# WFT0420CZ15_eval.net
KiCad netlist of a schematic drawn in EAGLE
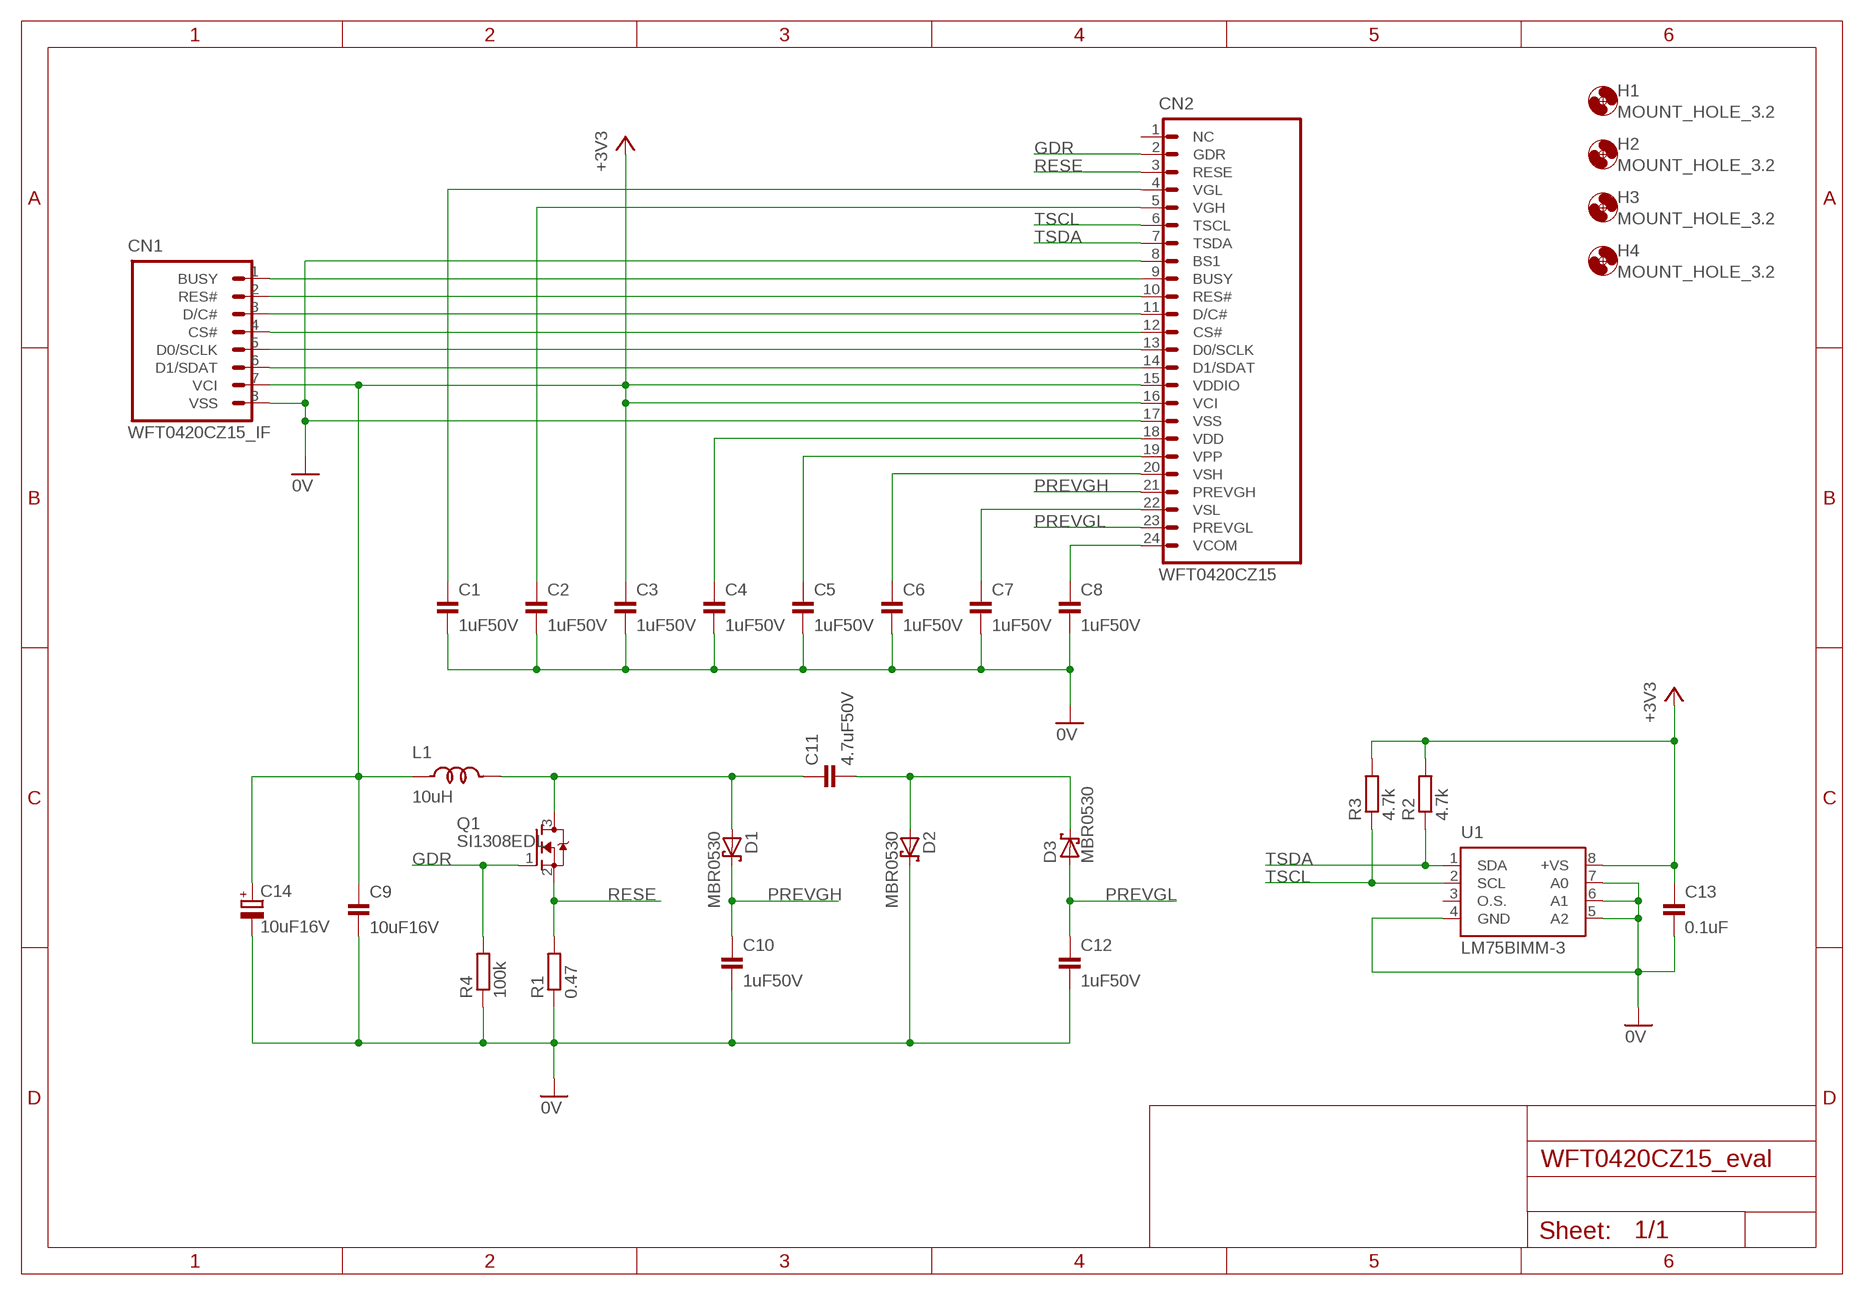
[diagram p0: schematic, sheet 1]

(export (version "E")
  (design (tool "Eeschema 10.0.6"))
  (components
    (comp (ref "C1")
      (value "1uF50V")
      (footprint "eagle-import:SMD_2012")
      (libsource (lib "eagle-import") (part "CAP_0805"))
    )
    (comp (ref "C2")
      (value "1uF50V")
      (footprint "eagle-import:SMD_2012")
      (libsource (lib "eagle-import") (part "CAP_0805"))
    )
    (comp (ref "C3")
      (value "1uF50V")
      (footprint "eagle-import:SMD_2012")
      (libsource (lib "eagle-import") (part "CAP_0805"))
    )
    (comp (ref "C4")
      (value "1uF50V")
      (footprint "eagle-import:SMD_2012")
      (libsource (lib "eagle-import") (part "CAP_0805"))
    )
    (comp (ref "C5")
      (value "1uF50V")
      (footprint "eagle-import:SMD_2012")
      (libsource (lib "eagle-import") (part "CAP_0805"))
    )
    (comp (ref "C6")
      (value "1uF50V")
      (footprint "eagle-import:SMD_2012")
      (libsource (lib "eagle-import") (part "CAP_0805"))
    )
    (comp (ref "C7")
      (value "1uF50V")
      (footprint "eagle-import:SMD_2012")
      (libsource (lib "eagle-import") (part "CAP_0805"))
    )
    (comp (ref "C8")
      (value "1uF50V")
      (footprint "eagle-import:SMD_2012")
      (libsource (lib "eagle-import") (part "CAP_0805"))
    )
    (comp (ref "C9")
      (value "10uF16V")
      (footprint "eagle-import:SMD_2012")
      (libsource (lib "eagle-import") (part "CAP_0805"))
    )
    (comp (ref "C10")
      (value "1uF50V")
      (footprint "eagle-import:SMD_2012")
      (libsource (lib "eagle-import") (part "CAP_0805"))
    )
    (comp (ref "C11")
      (value "4.7uF50V")
      (footprint "eagle-import:SMD_2012")
      (libsource (lib "eagle-import") (part "CAP_0805"))
    )
    (comp (ref "C12")
      (value "1uF50V")
      (footprint "eagle-import:SMD_2012")
      (libsource (lib "eagle-import") (part "CAP_0805"))
    )
    (comp (ref "C13")
      (value "0.1uF")
      (footprint "eagle-import:SMD_2012")
      (libsource (lib "eagle-import") (part "CAP_0805"))
    )
    (comp (ref "C14")
      (value "10uF16V")
      (footprint "eagle-import:C1210")
      (libsource (lib "eagle-import") (part "TPST106K016R0800"))
    )
    (comp (ref "CN1")
      (value "WFT0420CZ15_IF")
      (footprint "eagle-import:WFT0420CZ15_IF_8PIN")
      (libsource (lib "eagle-import") (part "WFT0420CZ15_IF"))
    )
    (comp (ref "CN2")
      (value "WFT0420CZ15")
      (footprint "eagle-import:FCB05-24P-REVERSE")
      (libsource (lib "eagle-import") (part "WFT0420CZ15"))
    )
    (comp (ref "D1")
      (value "MBR0530")
      (footprint "eagle-import:MBR0530")
      (libsource (lib "eagle-import") (part "MBR0530"))
    )
    (comp (ref "D2")
      (value "MBR0530")
      (footprint "eagle-import:MBR0530")
      (libsource (lib "eagle-import") (part "MBR0530"))
    )
    (comp (ref "D3")
      (value "MBR0530")
      (footprint "eagle-import:MBR0530")
      (libsource (lib "eagle-import") (part "MBR0530"))
    )
    (comp (ref "H1")
      (value "MOUNT_HOLE_3.2")
      (footprint "eagle-import:3,2")
      (libsource (lib "eagle-import") (part "MOUNT_HOLE_3.2"))
    )
    (comp (ref "H2")
      (value "MOUNT_HOLE_3.2")
      (footprint "eagle-import:3,2")
      (libsource (lib "eagle-import") (part "MOUNT_HOLE_3.2"))
    )
    (comp (ref "H3")
      (value "MOUNT_HOLE_3.2")
      (footprint "eagle-import:3,2")
      (libsource (lib "eagle-import") (part "MOUNT_HOLE_3.2"))
    )
    (comp (ref "H4")
      (value "MOUNT_HOLE_3.2")
      (footprint "eagle-import:3,2")
      (libsource (lib "eagle-import") (part "MOUNT_HOLE_3.2"))
    )
    (comp (ref "L1")
      (value "10uH")
      (footprint "eagle-import:NLCV25T")
      (libsource (lib "eagle-import") (part "NLCV25T"))
    )
    (comp (ref "Q1")
      (value "SI1308EDL")
      (footprint "eagle-import:SOT323")
      (libsource (lib "eagle-import") (part "SI1308EDL"))
    )
    (comp (ref "R1")
      (value "0.47")
      (footprint "eagle-import:SMD_2012")
      (libsource (lib "eagle-import") (part "RESISTOR_0805"))
    )
    (comp (ref "R2")
      (value "4.7k")
      (footprint "eagle-import:SMD_2012")
      (libsource (lib "eagle-import") (part "RESISTOR_0805"))
    )
    (comp (ref "R3")
      (value "4.7k")
      (footprint "eagle-import:SMD_2012")
      (libsource (lib "eagle-import") (part "RESISTOR_0805"))
    )
    (comp (ref "R4")
      (value "100k")
      (footprint "eagle-import:SMD_2012")
      (libsource (lib "eagle-import") (part "RESISTOR_0805"))
    )
    (comp (ref "U1")
      (value "LM75BIMM-3")
      (footprint "eagle-import:SSOP8-DGK")
      (libsource (lib "eagle-import") (part "LM75BIMM-3"))
    )
  )
  (nets
    (net (code "1") (name "+3V3") (class "Default")
      (node (ref "C13") (pin "1") (pinfunction "1_1") (pintype "passive"))
      (node (ref "C14") (pin "1") (pinfunction "+_1") (pintype "passive"))
      (node (ref "C3") (pin "1") (pinfunction "1_1") (pintype "passive"))
      (node (ref "C9") (pin "1") (pinfunction "1_1") (pintype "passive"))
      (node (ref "CN1") (pin "7") (pinfunction "VCI_7") (pintype "passive"))
      (node (ref "CN2") (pin "15") (pinfunction "VDDIO_15") (pintype "passive"))
      (node (ref "CN2") (pin "16") (pinfunction "VCI_16") (pintype "passive"))
      (node (ref "L1") (pin "1") (pinfunction "1_1") (pintype "passive"))
      (node (ref "R2") (pin "2") (pinfunction "2_2") (pintype "passive"))
      (node (ref "R3") (pin "2") (pinfunction "2_2") (pintype "passive"))
      (node (ref "U1") (pin "8") (pinfunction "+VS_8") (pintype "passive"))
    )
    (net (code "2") (name "/GDR") (class "Default")
      (node (ref "CN2") (pin "2") (pinfunction "GDR_2") (pintype "bidirectional"))
      (node (ref "Q1") (pin "1") (pinfunction "G_1") (pintype "passive"))
      (node (ref "R4") (pin "2") (pinfunction "2_2") (pintype "passive"))
    )
    (net (code "3") (name "/PREVGH") (class "Default")
      (node (ref "C10") (pin "1") (pinfunction "1_1") (pintype "passive"))
      (node (ref "CN2") (pin "21") (pinfunction "PREVGH_21") (pintype "passive"))
      (node (ref "D1") (pin "1") (pinfunction "C_1") (pintype "passive"))
    )
    (net (code "4") (name "/PREVGL") (class "Default")
      (node (ref "C12") (pin "1") (pinfunction "1_1") (pintype "passive"))
      (node (ref "CN2") (pin "23") (pinfunction "PREVGL_23") (pintype "passive"))
      (node (ref "D3") (pin "2") (pinfunction "A_2") (pintype "passive"))
    )
    (net (code "5") (name "/RESE") (class "Default")
      (node (ref "CN2") (pin "3") (pinfunction "RESE_3") (pintype "bidirectional"))
      (node (ref "Q1") (pin "2") (pinfunction "S_2") (pintype "passive"))
      (node (ref "R1") (pin "2") (pinfunction "2_2") (pintype "passive"))
    )
    (net (code "6") (name "/TSCL") (class "Default")
      (node (ref "CN2") (pin "6") (pinfunction "TSCL_6") (pintype "bidirectional"))
      (node (ref "R3") (pin "1") (pinfunction "1_1") (pintype "passive"))
      (node (ref "U1") (pin "2") (pinfunction "SCL_2") (pintype "bidirectional"))
    )
    (net (code "7") (name "/TSDA") (class "Default")
      (node (ref "CN2") (pin "7") (pinfunction "TSDA_7") (pintype "bidirectional"))
      (node (ref "R2") (pin "1") (pinfunction "1_1") (pintype "passive"))
      (node (ref "U1") (pin "1") (pinfunction "SDA_1") (pintype "bidirectional"))
    )
    (net (code "8") (name "0V") (class "Default")
      (node (ref "C1") (pin "2") (pinfunction "2_2") (pintype "passive"))
      (node (ref "C10") (pin "2") (pinfunction "2_2") (pintype "passive"))
      (node (ref "C12") (pin "2") (pinfunction "2_2") (pintype "passive"))
      (node (ref "C13") (pin "2") (pinfunction "2_2") (pintype "passive"))
      (node (ref "C14") (pin "2") (pinfunction "-_2") (pintype "passive"))
      (node (ref "C2") (pin "2") (pinfunction "2_2") (pintype "passive"))
      (node (ref "C3") (pin "2") (pinfunction "2_2") (pintype "passive"))
      (node (ref "C4") (pin "2") (pinfunction "2_2") (pintype "passive"))
      (node (ref "C5") (pin "2") (pinfunction "2_2") (pintype "passive"))
      (node (ref "C6") (pin "2") (pinfunction "2_2") (pintype "passive"))
      (node (ref "C7") (pin "2") (pinfunction "2_2") (pintype "passive"))
      (node (ref "C8") (pin "2") (pinfunction "2_2") (pintype "passive"))
      (node (ref "C9") (pin "2") (pinfunction "2_2") (pintype "passive"))
      (node (ref "CN1") (pin "8") (pinfunction "VSS_8") (pintype "passive"))
      (node (ref "CN2") (pin "17") (pinfunction "VSS_17") (pintype "passive"))
      (node (ref "CN2") (pin "8") (pinfunction "BS1_8") (pintype "bidirectional"))
      (node (ref "D2") (pin "1") (pinfunction "C_1") (pintype "passive"))
      (node (ref "R1") (pin "1") (pinfunction "1_1") (pintype "passive"))
      (node (ref "R4") (pin "1") (pinfunction "1_1") (pintype "passive"))
      (node (ref "U1") (pin "4") (pinfunction "GND_4") (pintype "passive"))
      (node (ref "U1") (pin "5") (pinfunction "A2_5") (pintype "bidirectional"))
      (node (ref "U1") (pin "6") (pinfunction "A1_6") (pintype "bidirectional"))
      (node (ref "U1") (pin "7") (pinfunction "A0_7") (pintype "bidirectional"))
    )
    (net (code "9") (name "Net-(CN1-BUSY)") (class "Default")
      (node (ref "CN1") (pin "1") (pinfunction "BUSY_1") (pintype "bidirectional"))
      (node (ref "CN2") (pin "9") (pinfunction "BUSY_9") (pintype "bidirectional"))
    )
    (net (code "10") (name "Net-(CN1-CS#)") (class "Default")
      (node (ref "CN1") (pin "4") (pinfunction "CS#_4") (pintype "bidirectional"))
      (node (ref "CN2") (pin "12") (pinfunction "CS#_12") (pintype "bidirectional"))
    )
    (net (code "11") (name "Net-(CN1-D0{slash}SCLK)") (class "Default")
      (node (ref "CN1") (pin "5") (pinfunction "D0/SCLK_5") (pintype "bidirectional"))
      (node (ref "CN2") (pin "13") (pinfunction "D0/SCLK_13") (pintype "bidirectional"))
    )
    (net (code "12") (name "Net-(CN1-D1{slash}SDAT)") (class "Default")
      (node (ref "CN1") (pin "6") (pinfunction "D1/SDAT_6") (pintype "bidirectional"))
      (node (ref "CN2") (pin "14") (pinfunction "D1/SDAT_14") (pintype "bidirectional"))
    )
    (net (code "13") (name "Net-(CN1-D{slash}C#)") (class "Default")
      (node (ref "CN1") (pin "3") (pinfunction "D/C#_3") (pintype "bidirectional"))
      (node (ref "CN2") (pin "11") (pinfunction "D/C#_11") (pintype "bidirectional"))
    )
    (net (code "14") (name "Net-(CN1-RES#)") (class "Default")
      (node (ref "CN1") (pin "2") (pinfunction "RES#_2") (pintype "bidirectional"))
      (node (ref "CN2") (pin "10") (pinfunction "RES#_10") (pintype "bidirectional"))
    )
    (net (code "15") (name "Net-(CN2-VCOM)") (class "Default")
      (node (ref "C8") (pin "1") (pinfunction "1_1") (pintype "passive"))
      (node (ref "CN2") (pin "24") (pinfunction "VCOM_24") (pintype "passive"))
    )
    (net (code "16") (name "Net-(CN2-VDD)") (class "Default")
      (node (ref "C4") (pin "1") (pinfunction "1_1") (pintype "passive"))
      (node (ref "CN2") (pin "18") (pinfunction "VDD_18") (pintype "passive"))
    )
    (net (code "17") (name "Net-(CN2-VGH)") (class "Default")
      (node (ref "C2") (pin "1") (pinfunction "1_1") (pintype "passive"))
      (node (ref "CN2") (pin "5") (pinfunction "VGH_5") (pintype "passive"))
    )
    (net (code "18") (name "Net-(CN2-VGL)") (class "Default")
      (node (ref "C1") (pin "1") (pinfunction "1_1") (pintype "passive"))
      (node (ref "CN2") (pin "4") (pinfunction "VGL_4") (pintype "passive"))
    )
    (net (code "19") (name "Net-(CN2-VPP)") (class "Default")
      (node (ref "C5") (pin "1") (pinfunction "1_1") (pintype "passive"))
      (node (ref "CN2") (pin "19") (pinfunction "VPP_19") (pintype "passive"))
    )
    (net (code "20") (name "Net-(CN2-VSH)") (class "Default")
      (node (ref "C6") (pin "1") (pinfunction "1_1") (pintype "passive"))
      (node (ref "CN2") (pin "20") (pinfunction "VSH_20") (pintype "passive"))
    )
    (net (code "21") (name "Net-(CN2-VSL)") (class "Default")
      (node (ref "C7") (pin "1") (pinfunction "1_1") (pintype "passive"))
      (node (ref "CN2") (pin "22") (pinfunction "VSL_22") (pintype "passive"))
    )
    (net (code "22") (name "Net-(D1-A)") (class "Default")
      (node (ref "C11") (pin "1") (pinfunction "1_1") (pintype "passive"))
      (node (ref "D1") (pin "2") (pinfunction "A_2") (pintype "passive"))
      (node (ref "L1") (pin "2") (pinfunction "2_2") (pintype "passive"))
      (node (ref "Q1") (pin "3") (pinfunction "D_3") (pintype "passive"))
    )
    (net (code "23") (name "Net-(D2-A)") (class "Default")
      (node (ref "C11") (pin "2") (pinfunction "2_2") (pintype "passive"))
      (node (ref "D2") (pin "2") (pinfunction "A_2") (pintype "passive"))
      (node (ref "D3") (pin "1") (pinfunction "C_1") (pintype "passive"))
    )
    (net (code "24") (name "unconnected-(CN2-NC-Pad1)") (class "Default")
      (node (ref "CN2") (pin "1") (pinfunction "NC_1") (pintype "no_connect"))
    )
    (net (code "25") (name "unconnected-(U1-O.S.-Pad3)") (class "Default")
      (node (ref "U1") (pin "3") (pinfunction "O.S._3") (pintype "bidirectional"))
    )
  )
)
